# Analog_Output.net
KiCad netlist of a schematic drawn in Altium Designer
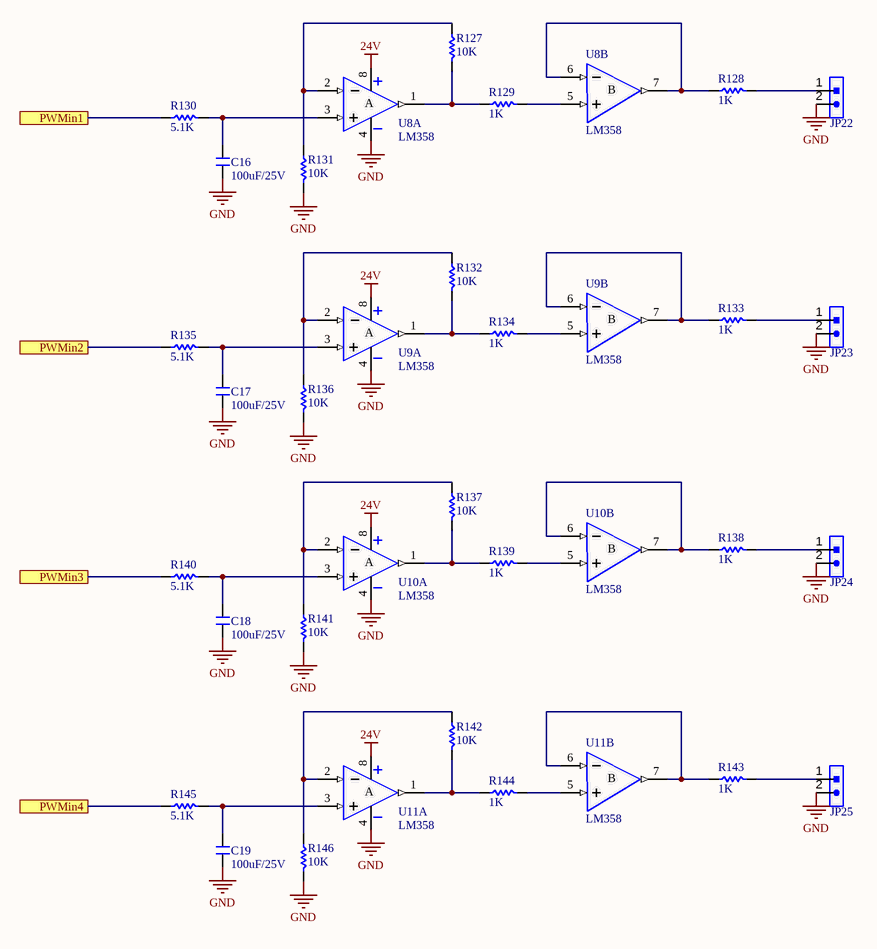
[diagram p0: Analog Output.SchDoc]

(export (version "E")
  (design (tool "Eeschema 10.0.6"))
  (components
    (comp (ref "C16")
      (value "100uF/25V")
      (footprint "C 0805")
      (description "Non-polar patch capacitor")
      (fields (field (name "版权归属") "源创客"))
      (libsource (lib "Passive (Resistor-Capacitor-Inductor-Veristor-Ferrite)") (part "C"))
    )
    (comp (ref "C17")
      (value "100uF/25V")
      (footprint "C 0805")
      (description "Non-polar patch capacitor")
      (fields (field (name "版权归属") "源创客"))
      (libsource (lib "Passive (Resistor-Capacitor-Inductor-Veristor-Ferrite)") (part "C"))
    )
    (comp (ref "C18")
      (value "100uF/25V")
      (footprint "C 0805")
      (description "Non-polar patch capacitor")
      (fields (field (name "版权归属") "源创客"))
      (libsource (lib "Passive (Resistor-Capacitor-Inductor-Veristor-Ferrite)") (part "C"))
    )
    (comp (ref "C19")
      (value "100uF/25V")
      (footprint "C 0805")
      (description "Non-polar patch capacitor")
      (fields (field (name "版权归属") "源创客"))
      (libsource (lib "Passive (Resistor-Capacitor-Inductor-Veristor-Ferrite)") (part "C"))
    )
    (comp (ref "JP22")
      (value "HDR-1X2")
      (footprint "KF301-2P")
      (description "2P Connector")
      (fields (field (name "版权归属") "源创客"))
      (libsource (lib "Connectors") (part "Header 2"))
    )
    (comp (ref "JP23")
      (value "HDR-1X2")
      (footprint "KF301-2P")
      (description "2P Connector")
      (fields (field (name "版权归属") "源创客"))
      (libsource (lib "Connectors") (part "Header 2"))
    )
    (comp (ref "JP24")
      (value "HDR-1X2")
      (footprint "KF301-2P")
      (description "2P Connector")
      (fields (field (name "版权归属") "源创客"))
      (libsource (lib "Connectors") (part "Header 2"))
    )
    (comp (ref "JP25")
      (value "HDR-1X2")
      (footprint "KF301-2P")
      (description "2P Connector")
      (fields (field (name "版权归属") "源创客"))
      (libsource (lib "Connectors") (part "Header 2"))
    )
    (comp (ref "R127")
      (value "10K")
      (footprint "R 0805")
      (description "Chip resistor")
      (fields (field (name "版权归属") "源创客"))
      (libsource (lib "Passive (Resistor-Capacitor-Inductor-Veristor-Ferrite)") (part "R"))
    )
    (comp (ref "R128")
      (value "1K")
      (footprint "R 0805")
      (description "Chip resistor")
      (fields (field (name "版权归属") "源创客"))
      (libsource (lib "Passive (Resistor-Capacitor-Inductor-Veristor-Ferrite)") (part "R"))
    )
    (comp (ref "R129")
      (value "1K")
      (footprint "R 0805")
      (description "Chip resistor")
      (fields (field (name "版权归属") "源创客"))
      (libsource (lib "Passive (Resistor-Capacitor-Inductor-Veristor-Ferrite)") (part "R"))
    )
    (comp (ref "R130")
      (value "5.1K")
      (footprint "R 0805")
      (description "Chip resistor")
      (fields (field (name "版权归属") "源创客"))
      (libsource (lib "Passive (Resistor-Capacitor-Inductor-Veristor-Ferrite)") (part "R"))
    )
    (comp (ref "R131")
      (value "10K")
      (footprint "R 0805")
      (description "Chip resistor")
      (fields (field (name "版权归属") "源创客"))
      (libsource (lib "Passive (Resistor-Capacitor-Inductor-Veristor-Ferrite)") (part "R"))
    )
    (comp (ref "R132")
      (value "10K")
      (footprint "R 0805")
      (description "Chip resistor")
      (fields (field (name "版权归属") "源创客"))
      (libsource (lib "Passive (Resistor-Capacitor-Inductor-Veristor-Ferrite)") (part "R"))
    )
    (comp (ref "R133")
      (value "1K")
      (footprint "R 0805")
      (description "Chip resistor")
      (fields (field (name "版权归属") "源创客"))
      (libsource (lib "Passive (Resistor-Capacitor-Inductor-Veristor-Ferrite)") (part "R"))
    )
    (comp (ref "R134")
      (value "1K")
      (footprint "R 0805")
      (description "Chip resistor")
      (fields (field (name "版权归属") "源创客"))
      (libsource (lib "Passive (Resistor-Capacitor-Inductor-Veristor-Ferrite)") (part "R"))
    )
    (comp (ref "R135")
      (value "5.1K")
      (footprint "R 0805")
      (description "Chip resistor")
      (fields (field (name "版权归属") "源创客"))
      (libsource (lib "Passive (Resistor-Capacitor-Inductor-Veristor-Ferrite)") (part "R"))
    )
    (comp (ref "R136")
      (value "10K")
      (footprint "R 0805")
      (description "Chip resistor")
      (fields (field (name "版权归属") "源创客"))
      (libsource (lib "Passive (Resistor-Capacitor-Inductor-Veristor-Ferrite)") (part "R"))
    )
    (comp (ref "R137")
      (value "10K")
      (footprint "R 0805")
      (description "Chip resistor")
      (fields (field (name "版权归属") "源创客"))
      (libsource (lib "Passive (Resistor-Capacitor-Inductor-Veristor-Ferrite)") (part "R"))
    )
    (comp (ref "R138")
      (value "1K")
      (footprint "R 0805")
      (description "Chip resistor")
      (fields (field (name "版权归属") "源创客"))
      (libsource (lib "Passive (Resistor-Capacitor-Inductor-Veristor-Ferrite)") (part "R"))
    )
    (comp (ref "R139")
      (value "1K")
      (footprint "R 0805")
      (description "Chip resistor")
      (fields (field (name "版权归属") "源创客"))
      (libsource (lib "Passive (Resistor-Capacitor-Inductor-Veristor-Ferrite)") (part "R"))
    )
    (comp (ref "R140")
      (value "5.1K")
      (footprint "R 0805")
      (description "Chip resistor")
      (fields (field (name "版权归属") "源创客"))
      (libsource (lib "Passive (Resistor-Capacitor-Inductor-Veristor-Ferrite)") (part "R"))
    )
    (comp (ref "R141")
      (value "10K")
      (footprint "R 0805")
      (description "Chip resistor")
      (fields (field (name "版权归属") "源创客"))
      (libsource (lib "Passive (Resistor-Capacitor-Inductor-Veristor-Ferrite)") (part "R"))
    )
    (comp (ref "R142")
      (value "10K")
      (footprint "R 0805")
      (description "Chip resistor")
      (fields (field (name "版权归属") "源创客"))
      (libsource (lib "Passive (Resistor-Capacitor-Inductor-Veristor-Ferrite)") (part "R"))
    )
    (comp (ref "R143")
      (value "1K")
      (footprint "R 0805")
      (description "Chip resistor")
      (fields (field (name "版权归属") "源创客"))
      (libsource (lib "Passive (Resistor-Capacitor-Inductor-Veristor-Ferrite)") (part "R"))
    )
    (comp (ref "R144")
      (value "1K")
      (footprint "R 0805")
      (description "Chip resistor")
      (fields (field (name "版权归属") "源创客"))
      (libsource (lib "Passive (Resistor-Capacitor-Inductor-Veristor-Ferrite)") (part "R"))
    )
    (comp (ref "R145")
      (value "5.1K")
      (footprint "R 0805")
      (description "Chip resistor")
      (fields (field (name "版权归属") "源创客"))
      (libsource (lib "Passive (Resistor-Capacitor-Inductor-Veristor-Ferrite)") (part "R"))
    )
    (comp (ref "R146")
      (value "10K")
      (footprint "R 0805")
      (description "Chip resistor")
      (fields (field (name "版权归属") "源创客"))
      (libsource (lib "Passive (Resistor-Capacitor-Inductor-Veristor-Ferrite)") (part "R"))
    )
    (comp (ref "U8")
      (value "LM358")
      (footprint "SOP8_N")
      (description "Dual op amp")
      (fields (field (name "版权归属") "源创客"))
      (libsource (lib "Integrated Circuit") (part "LM358"))
    )
    (comp (ref "U9")
      (value "LM358")
      (footprint "SOP8_N")
      (description "Dual op amp")
      (fields (field (name "版权归属") "源创客"))
      (libsource (lib "Integrated Circuit") (part "LM358"))
    )
    (comp (ref "U10")
      (value "LM358")
      (footprint "SOP8_N")
      (description "Dual op amp")
      (fields (field (name "版权归属") "源创客"))
      (libsource (lib "Integrated Circuit") (part "LM358"))
    )
    (comp (ref "U11")
      (value "LM358")
      (footprint "SOP8_N")
      (description "Dual op amp")
      (fields (field (name "版权归属") "源创客"))
      (libsource (lib "Integrated Circuit") (part "LM358"))
    )
  )
  (nets
    (net (code "1") (name "/PWMin1") (class "Default")
      (node (ref "R130") (pin "1") (pinfunction "1_1") (pintype "passive"))
    )
    (net (code "2") (name "/PWMin2") (class "Default")
      (node (ref "R135") (pin "1") (pinfunction "1_1") (pintype "passive"))
    )
    (net (code "3") (name "/PWMin3") (class "Default")
      (node (ref "R140") (pin "1") (pinfunction "1_1") (pintype "passive"))
    )
    (net (code "4") (name "/PWMin4") (class "Default")
      (node (ref "R145") (pin "1") (pinfunction "1_1") (pintype "passive"))
    )
    (net (code "5") (name "24V") (class "Default")
      (node (ref "U10") (pin "8") (pinfunction "VCC+_8") (pintype "power_in"))
      (node (ref "U11") (pin "8") (pinfunction "VCC+_8") (pintype "power_in"))
      (node (ref "U8") (pin "8") (pinfunction "VCC+_8") (pintype "power_in"))
      (node (ref "U9") (pin "8") (pinfunction "VCC+_8") (pintype "power_in"))
    )
    (net (code "6") (name "GND") (class "Default")
      (node (ref "C16") (pin "2") (pinfunction "2_2") (pintype "passive"))
      (node (ref "C17") (pin "2") (pinfunction "2_2") (pintype "passive"))
      (node (ref "C18") (pin "2") (pinfunction "2_2") (pintype "passive"))
      (node (ref "C19") (pin "2") (pinfunction "2_2") (pintype "passive"))
      (node (ref "JP22") (pin "2") (pintype "passive"))
      (node (ref "JP23") (pin "2") (pintype "passive"))
      (node (ref "JP24") (pin "2") (pintype "passive"))
      (node (ref "JP25") (pin "2") (pintype "passive"))
      (node (ref "R131") (pin "2") (pinfunction "2_2") (pintype "passive"))
      (node (ref "R136") (pin "2") (pinfunction "2_2") (pintype "passive"))
      (node (ref "R141") (pin "2") (pinfunction "2_2") (pintype "passive"))
      (node (ref "R146") (pin "2") (pinfunction "2_2") (pintype "passive"))
      (node (ref "U10") (pin "4") (pinfunction "VCC-_4") (pintype "power_in"))
      (node (ref "U11") (pin "4") (pinfunction "VCC-_4") (pintype "power_in"))
      (node (ref "U8") (pin "4") (pinfunction "VCC-_4") (pintype "power_in"))
      (node (ref "U9") (pin "4") (pinfunction "VCC-_4") (pintype "power_in"))
    )
    (net (code "7") (name "Net-(JP22-Pad1)") (class "Default")
      (node (ref "JP22") (pin "1") (pintype "passive"))
      (node (ref "R128") (pin "2") (pinfunction "2_2") (pintype "passive"))
    )
    (net (code "8") (name "Net-(JP23-Pad1)") (class "Default")
      (node (ref "JP23") (pin "1") (pintype "passive"))
      (node (ref "R133") (pin "2") (pinfunction "2_2") (pintype "passive"))
    )
    (net (code "9") (name "Net-(JP24-Pad1)") (class "Default")
      (node (ref "JP24") (pin "1") (pintype "passive"))
      (node (ref "R138") (pin "2") (pinfunction "2_2") (pintype "passive"))
    )
    (net (code "10") (name "Net-(JP25-Pad1)") (class "Default")
      (node (ref "JP25") (pin "1") (pintype "passive"))
      (node (ref "R143") (pin "2") (pinfunction "2_2") (pintype "passive"))
    )
    (net (code "11") (name "Net-(U8A-IN1+)") (class "Default")
      (node (ref "C16") (pin "1") (pinfunction "1_1") (pintype "passive"))
      (node (ref "R130") (pin "2") (pinfunction "2_2") (pintype "passive"))
      (node (ref "U8") (pin "3") (pinfunction "IN1+_3") (pintype "input"))
    )
    (net (code "12") (name "Net-(U8A-IN1-)") (class "Default")
      (node (ref "R127") (pin "1") (pinfunction "1_1") (pintype "passive"))
      (node (ref "R131") (pin "1") (pinfunction "1_1") (pintype "passive"))
      (node (ref "U8") (pin "2") (pinfunction "IN1-_2") (pintype "input"))
    )
    (net (code "13") (name "Net-(U8A-OUT1)") (class "Default")
      (node (ref "R127") (pin "2") (pinfunction "2_2") (pintype "passive"))
      (node (ref "R129") (pin "1") (pinfunction "1_1") (pintype "passive"))
      (node (ref "U8") (pin "1") (pinfunction "OUT1_1") (pintype "output"))
    )
    (net (code "14") (name "Net-(U8B-IN2+)") (class "Default")
      (node (ref "R129") (pin "2") (pinfunction "2_2") (pintype "passive"))
      (node (ref "U8") (pin "5") (pinfunction "IN2+_5") (pintype "input"))
    )
    (net (code "15") (name "Net-(U8B-IN2-)") (class "Default")
      (node (ref "R128") (pin "1") (pinfunction "1_1") (pintype "passive"))
      (node (ref "U8") (pin "6") (pinfunction "IN2-_6") (pintype "input"))
      (node (ref "U8") (pin "7") (pinfunction "OUT2_7") (pintype "output"))
    )
    (net (code "16") (name "Net-(U9A-IN1+)") (class "Default")
      (node (ref "C17") (pin "1") (pinfunction "1_1") (pintype "passive"))
      (node (ref "R135") (pin "2") (pinfunction "2_2") (pintype "passive"))
      (node (ref "U9") (pin "3") (pinfunction "IN1+_3") (pintype "input"))
    )
    (net (code "17") (name "Net-(U9A-IN1-)") (class "Default")
      (node (ref "R132") (pin "1") (pinfunction "1_1") (pintype "passive"))
      (node (ref "R136") (pin "1") (pinfunction "1_1") (pintype "passive"))
      (node (ref "U9") (pin "2") (pinfunction "IN1-_2") (pintype "input"))
    )
    (net (code "18") (name "Net-(U9A-OUT1)") (class "Default")
      (node (ref "R132") (pin "2") (pinfunction "2_2") (pintype "passive"))
      (node (ref "R134") (pin "1") (pinfunction "1_1") (pintype "passive"))
      (node (ref "U9") (pin "1") (pinfunction "OUT1_1") (pintype "output"))
    )
    (net (code "19") (name "Net-(U9B-IN2+)") (class "Default")
      (node (ref "R134") (pin "2") (pinfunction "2_2") (pintype "passive"))
      (node (ref "U9") (pin "5") (pinfunction "IN2+_5") (pintype "input"))
    )
    (net (code "20") (name "Net-(U9B-IN2-)") (class "Default")
      (node (ref "R133") (pin "1") (pinfunction "1_1") (pintype "passive"))
      (node (ref "U9") (pin "6") (pinfunction "IN2-_6") (pintype "input"))
      (node (ref "U9") (pin "7") (pinfunction "OUT2_7") (pintype "output"))
    )
    (net (code "21") (name "Net-(U10A-IN1+)") (class "Default")
      (node (ref "C18") (pin "1") (pinfunction "1_1") (pintype "passive"))
      (node (ref "R140") (pin "2") (pinfunction "2_2") (pintype "passive"))
      (node (ref "U10") (pin "3") (pinfunction "IN1+_3") (pintype "input"))
    )
    (net (code "22") (name "Net-(U10A-IN1-)") (class "Default")
      (node (ref "R137") (pin "1") (pinfunction "1_1") (pintype "passive"))
      (node (ref "R141") (pin "1") (pinfunction "1_1") (pintype "passive"))
      (node (ref "U10") (pin "2") (pinfunction "IN1-_2") (pintype "input"))
    )
    (net (code "23") (name "Net-(U10A-OUT1)") (class "Default")
      (node (ref "R137") (pin "2") (pinfunction "2_2") (pintype "passive"))
      (node (ref "R139") (pin "1") (pinfunction "1_1") (pintype "passive"))
      (node (ref "U10") (pin "1") (pinfunction "OUT1_1") (pintype "output"))
    )
    (net (code "24") (name "Net-(U10B-IN2+)") (class "Default")
      (node (ref "R139") (pin "2") (pinfunction "2_2") (pintype "passive"))
      (node (ref "U10") (pin "5") (pinfunction "IN2+_5") (pintype "input"))
    )
    (net (code "25") (name "Net-(U10B-IN2-)") (class "Default")
      (node (ref "R138") (pin "1") (pinfunction "1_1") (pintype "passive"))
      (node (ref "U10") (pin "6") (pinfunction "IN2-_6") (pintype "input"))
      (node (ref "U10") (pin "7") (pinfunction "OUT2_7") (pintype "output"))
    )
    (net (code "26") (name "Net-(U11A-IN1+)") (class "Default")
      (node (ref "C19") (pin "1") (pinfunction "1_1") (pintype "passive"))
      (node (ref "R145") (pin "2") (pinfunction "2_2") (pintype "passive"))
      (node (ref "U11") (pin "3") (pinfunction "IN1+_3") (pintype "input"))
    )
    (net (code "27") (name "Net-(U11A-IN1-)") (class "Default")
      (node (ref "R142") (pin "1") (pinfunction "1_1") (pintype "passive"))
      (node (ref "R146") (pin "1") (pinfunction "1_1") (pintype "passive"))
      (node (ref "U11") (pin "2") (pinfunction "IN1-_2") (pintype "input"))
    )
    (net (code "28") (name "Net-(U11A-OUT1)") (class "Default")
      (node (ref "R142") (pin "2") (pinfunction "2_2") (pintype "passive"))
      (node (ref "R144") (pin "1") (pinfunction "1_1") (pintype "passive"))
      (node (ref "U11") (pin "1") (pinfunction "OUT1_1") (pintype "output"))
    )
    (net (code "29") (name "Net-(U11B-IN2+)") (class "Default")
      (node (ref "R144") (pin "2") (pinfunction "2_2") (pintype "passive"))
      (node (ref "U11") (pin "5") (pinfunction "IN2+_5") (pintype "input"))
    )
    (net (code "30") (name "Net-(U11B-IN2-)") (class "Default")
      (node (ref "R143") (pin "1") (pinfunction "1_1") (pintype "passive"))
      (node (ref "U11") (pin "6") (pinfunction "IN2-_6") (pintype "input"))
      (node (ref "U11") (pin "7") (pinfunction "OUT2_7") (pintype "output"))
    )
  )
)
